# C4F7N_MainBoard.net
KiCad netlist of a schematic drawn in EasyEDA
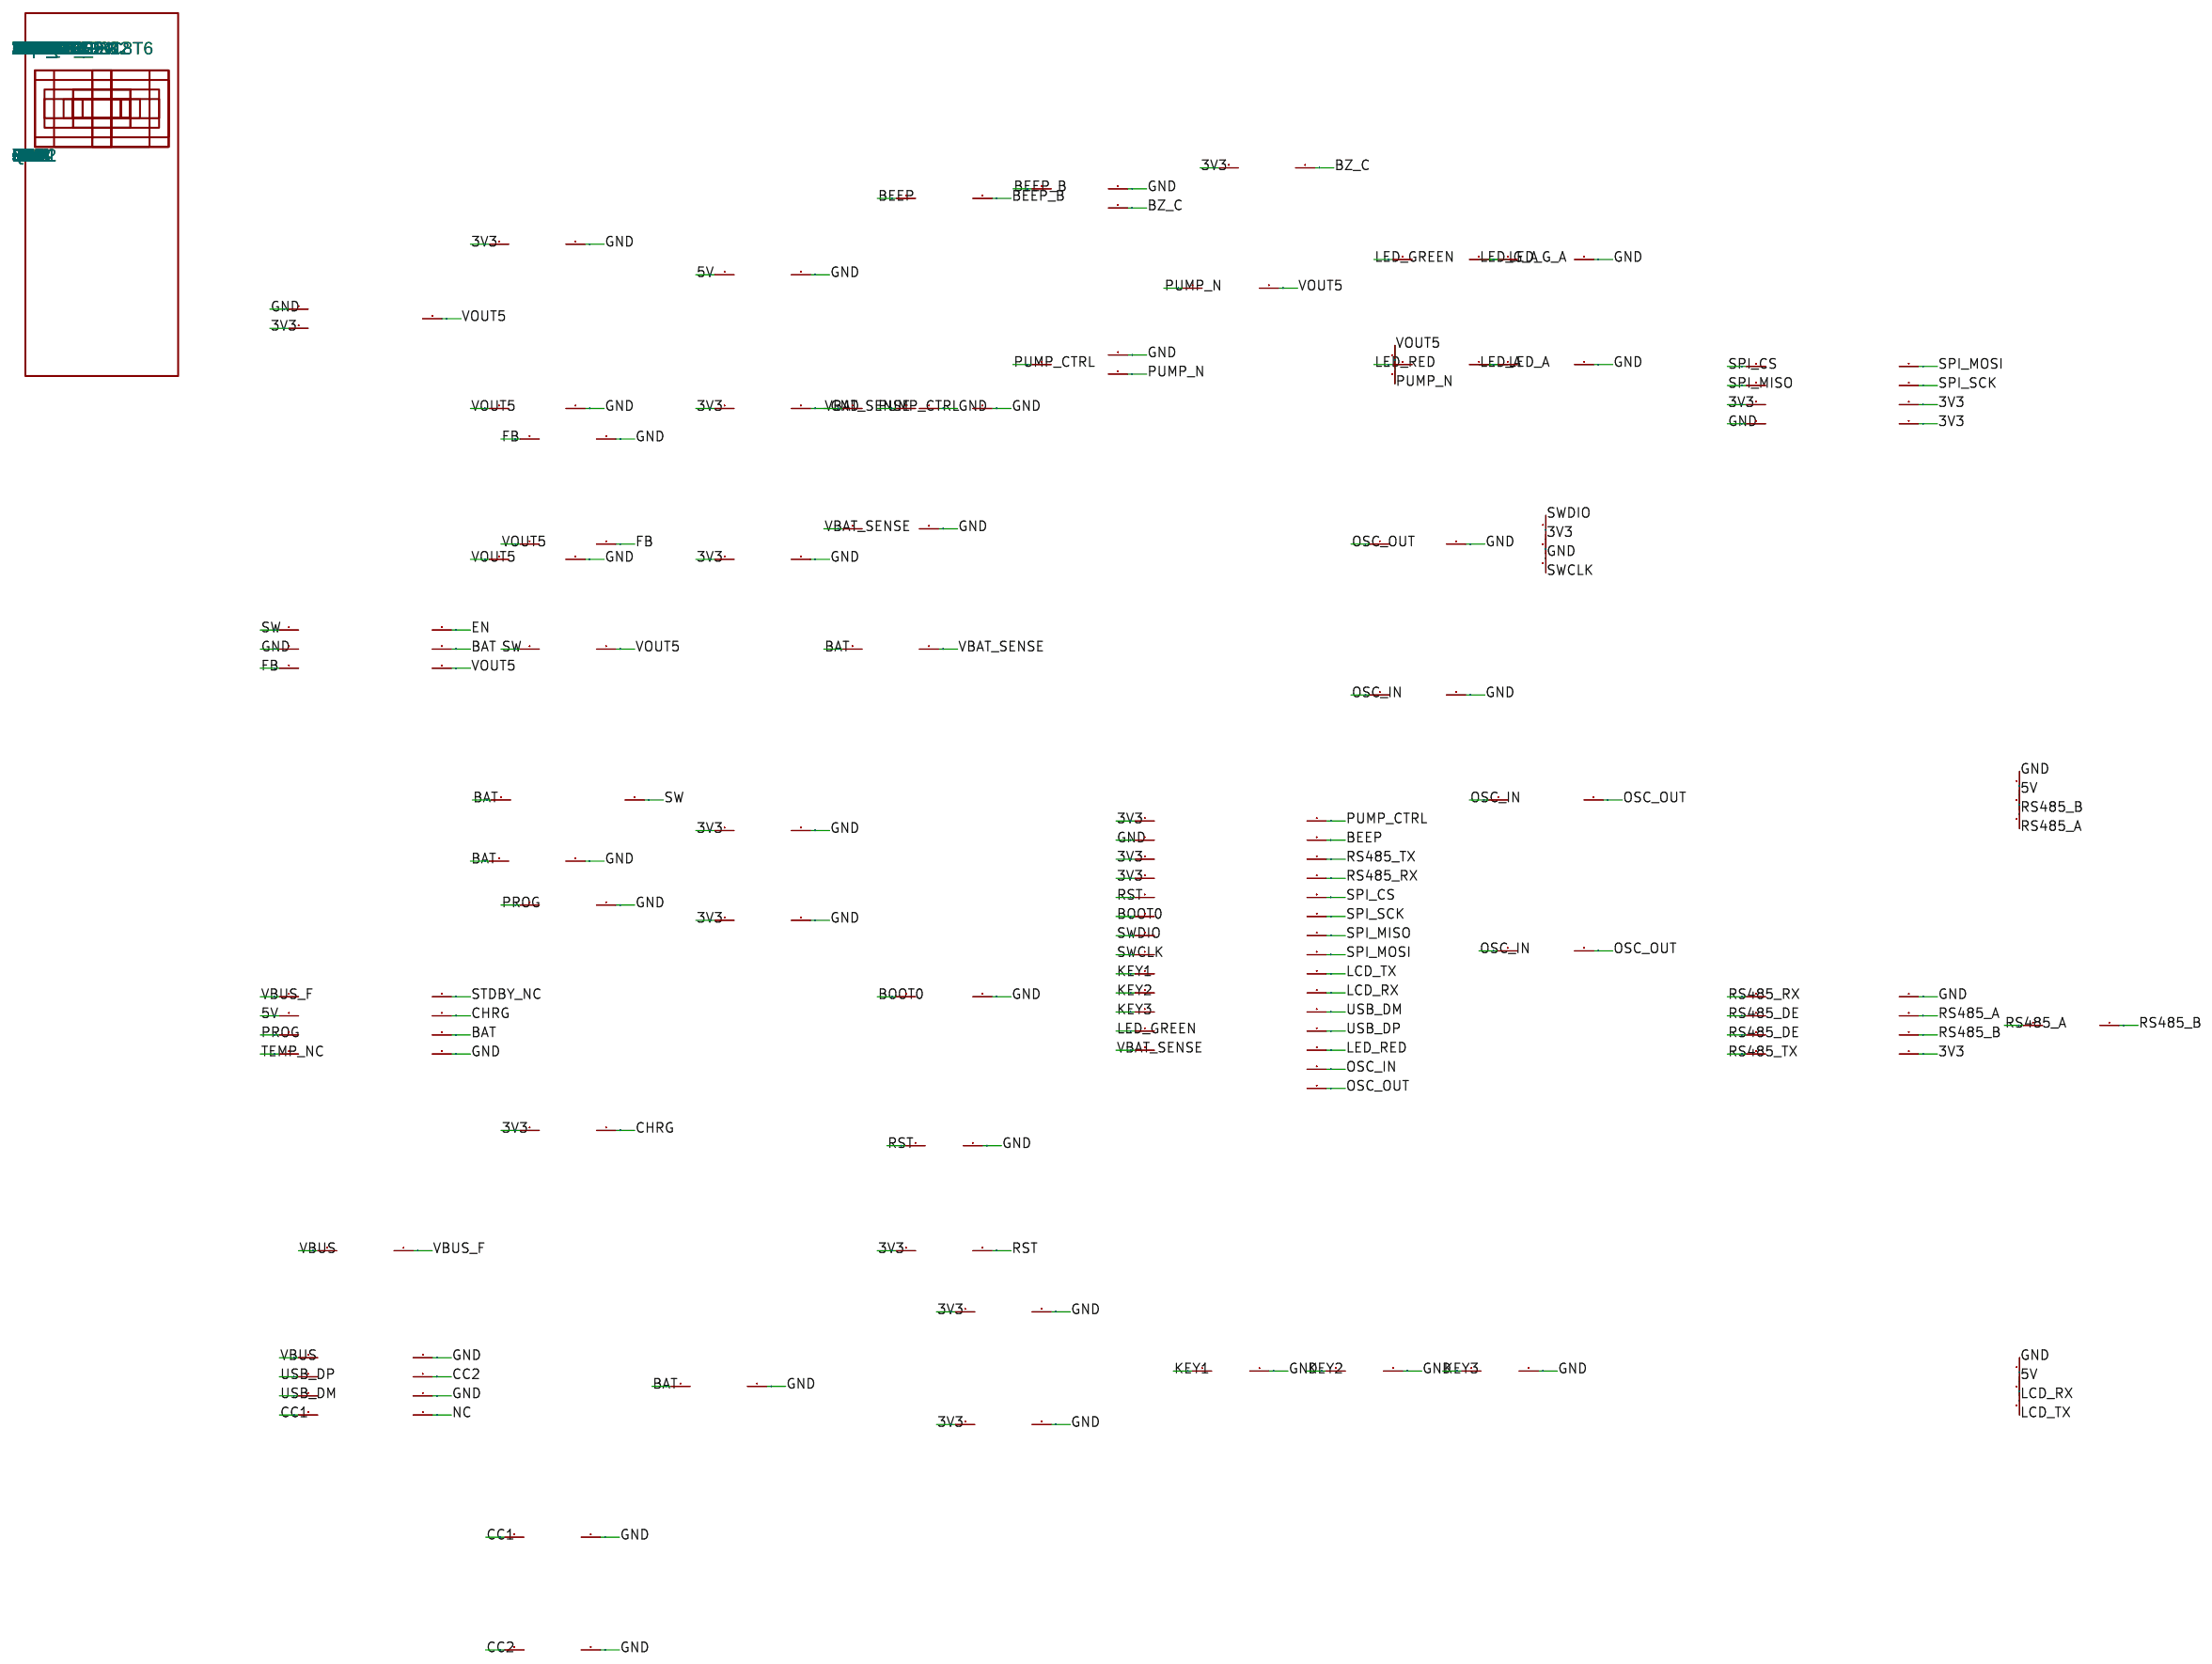
[diagram p0: schematic sheet]

(export (version "E")
  (design (tool "Eeschema 10.0.6"))
  (components
    (comp (ref "BT1") (value "18650x2") (libsource (lib "") (part "Unknown_323_669")))
    (comp (ref "BZ1") (value "BUZZER_5V") (libsource (lib "") (part "Unknown_610_31")))
    (comp (ref "C1") (value "10uF") (libsource (lib "") (part "Unknown_228_394")))
    (comp (ref "C2") (value "22uF") (libsource (lib "") (part "Unknown_228_236")))
    (comp (ref "C3") (value "10uF") (libsource (lib "") (part "Unknown_228_157")))
    (comp (ref "C4") (value "10uF") (libsource (lib "") (part "Unknown_228_71")))
    (comp (ref "C5") (value "100nF") (libsource (lib "") (part "Unknown_346_378")))
    (comp (ref "C6") (value "100nF") (libsource (lib "") (part "Unknown_346_425")))
    (comp (ref "C7") (value "20pF") (libsource (lib "") (part "Unknown_689_307")))
    (comp (ref "C8") (value "20pF") (libsource (lib "") (part "Unknown_689_228")))
    (comp (ref "C9") (value "100nF") (libsource (lib "") (part "Unknown_346_236")))
    (comp (ref "C10") (value "100nF") (libsource (lib "") (part "Unknown_346_157")))
    (comp (ref "C11") (value "100nF") (libsource (lib "") (part "Unknown_472_689")))
    (comp (ref "C12") (value "100nF") (libsource (lib "") (part "Unknown_472_630")))
    (comp (ref "C13") (value "100nF") (libsource (lib "") (part "Unknown_346_87")))
    (comp (ref "C14") (value "100nF") (libsource (lib "") (part "Unknown_413_157")))
    (comp (ref "D1") (value "LED_RED") (libsource (lib "") (part "Unknown_244_535")))
    (comp (ref "D2") (value "SS34") (libsource (lib "") (part "Unknown_244_283")))
    (comp (ref "D3") (value "1N5819") (libsource (lib "") (part "Unknown_591_94")))
    (comp (ref "F1") (value "500mA") (libsource (lib "") (part "Unknown_138_598")))
    (comp (ref "J1") (value "USB-C") (libsource (lib "") (part "Unknown_138_669")))
    (comp (ref "J2") (value "LCD_4.3") (libsource (lib "") (part "Unknown_1004_669")))
    (comp (ref "J3") (value "PROBE_GX12") (libsource (lib "") (part "Unknown_1004_362")))
    (comp (ref "J4") (value "PUMP") (libsource (lib "") (part "Unknown_677_134")))
    (comp (ref "J6") (value "SWD") (libsource (lib "") (part "Unknown_756_228")))
    (comp (ref "L1") (value "10uH") (libsource (lib "") (part "Unknown_244_362")))
    (comp (ref "LED1") (value "LED_RED") (libsource (lib "") (part "Unknown_756_134")))
    (comp (ref "LED2") (value "LED_GREEN") (libsource (lib "") (part "Unknown_756_79")))
    (comp (ref "Q1") (value "SI2302") (libsource (lib "") (part "Unknown_512_134")))
    (comp (ref "Q2") (value "MMBT2222") (libsource (lib "") (part "Unknown_512_47")))
    (comp (ref "R1") (value "1.2k") (libsource (lib "") (part "Unknown_244_417")))
    (comp (ref "R2") (value "100k") (libsource (lib "") (part "Unknown_244_228")))
    (comp (ref "R3") (value "20k") (libsource (lib "") (part "Unknown_244_173")))
    (comp (ref "R4") (value "1M") (libsource (lib "") (part "Unknown_756_441")))
    (comp (ref "R5") (value "10k") (libsource (lib "") (part "Unknown_441_598")))
    (comp (ref "R6") (value "10k") (libsource (lib "") (part "Unknown_441_465")))
    (comp (ref "R9") (value "120R") (libsource (lib "") (part "Unknown_1031_480")))
    (comp (ref "R12") (value "5.1k") (libsource (lib "") (part "Unknown_236_748")))
    (comp (ref "R13") (value "5.1k") (libsource (lib "") (part "Unknown_236_807")))
    (comp (ref "R15") (value "100k") (libsource (lib "") (part "Unknown_441_157")))
    (comp (ref "R16") (value "1k") (libsource (lib "") (part "Unknown_441_47")))
    (comp (ref "R17") (value "330R") (libsource (lib "") (part "Unknown_701_134")))
    (comp (ref "R18") (value "330R") (libsource (lib "") (part "Unknown_701_79")))
    (comp (ref "R22") (value "100k") (libsource (lib "") (part "Unknown_413_283")))
    (comp (ref "R23") (value "100k") (libsource (lib "") (part "Unknown_413_220")))
    (comp (ref "SW1") (value "RESET") (libsource (lib "") (part "Unknown_441_543")))
    (comp (ref "SW2") (value "KEY1") (libsource (lib "") (part "Unknown_591_661")))
    (comp (ref "SW3") (value "KEY2") (libsource (lib "") (part "Unknown_661_661")))
    (comp (ref "SW4") (value "KEY3") (libsource (lib "") (part "Unknown_732_661")))
    (comp (ref "U1") (value "TP4056") (libsource (lib "") (part "Unknown_138_480")))
    (comp (ref "U2") (value "MT3608") (libsource (lib "") (part "Unknown_138_283")))
    (comp (ref "U3") (value "AMS1117-3.3") (libsource (lib "") (part "Unknown_138_110")))
    (comp (ref "U4") (value "STM32F103C8T6") (libsource (lib "") (part "Unknown_591_413")))
    (comp (ref "U5") (value "MAX3485") (libsource (lib "") (part "Unknown_906_480")))
    (comp (ref "U6") (value "W25Q16") (libsource (lib "") (part "Unknown_906_150")))
    (comp (ref "Y1") (value "8MHz") (libsource (lib "") (part "Unknown_756_362")))
  )
  (nets
    (net (code "1") (name "/3V3") (class "Default")
      (node (ref "J2") (pin "2") (pinfunction "2_2") (pintype "unspecified"))
      (node (ref "J3") (pin "2") (pinfunction "2_2") (pintype "unspecified"))
      (node (ref "J6") (pin "2") (pinfunction "2_2") (pintype "unspecified"))
    )
    (net (code "24") (name "/PUMP_N") (class "Default")
      (node (ref "J4") (pin "2") (pinfunction "2_2") (pintype "unspecified"))
    )
    (net (code "40") (name "unconnected-(BT1-Pad2)") (class "Default")
      (node (ref "BT1") (pin "2") (pinfunction "2_2") (pintype "unspecified"))
    )
    (net (code "41") (name "unconnected-(BT1-Pad2)_1") (class "Default")
      (node (ref "BT1") (pin "2") (pinfunction "2_2") (pintype "unspecified"))
    )
    (net (code "42") (name "unconnected-(BZ1-Pad2)") (class "Default")
      (node (ref "BZ1") (pin "2") (pinfunction "2_2") (pintype "unspecified"))
    )
    (net (code "43") (name "unconnected-(BZ1-Pad2)_1") (class "Default")
      (node (ref "BZ1") (pin "2") (pinfunction "2_2") (pintype "unspecified"))
    )
    (net (code "44") (name "unconnected-(C1-Pad2)") (class "Default")
      (node (ref "C1") (pin "2") (pinfunction "2_2") (pintype "unspecified"))
    )
    (net (code "45") (name "unconnected-(C1-Pad2)_1") (class "Default")
      (node (ref "C1") (pin "2") (pinfunction "2_2") (pintype "unspecified"))
    )
    (net (code "46") (name "unconnected-(C2-Pad2)") (class "Default")
      (node (ref "C2") (pin "2") (pinfunction "2_2") (pintype "unspecified"))
    )
    (net (code "47") (name "unconnected-(C2-Pad2)_1") (class "Default")
      (node (ref "C2") (pin "2") (pinfunction "2_2") (pintype "unspecified"))
    )
    (net (code "48") (name "unconnected-(C3-Pad2)") (class "Default")
      (node (ref "C3") (pin "2") (pinfunction "2_2") (pintype "unspecified"))
    )
    (net (code "49") (name "unconnected-(C3-Pad2)_1") (class "Default")
      (node (ref "C3") (pin "2") (pinfunction "2_2") (pintype "unspecified"))
    )
    (net (code "50") (name "unconnected-(C4-Pad2)") (class "Default")
      (node (ref "C4") (pin "2") (pinfunction "2_2") (pintype "unspecified"))
    )
    (net (code "51") (name "unconnected-(C4-Pad2)_1") (class "Default")
      (node (ref "C4") (pin "2") (pinfunction "2_2") (pintype "unspecified"))
    )
    (net (code "52") (name "unconnected-(C5-Pad2)") (class "Default")
      (node (ref "C5") (pin "2") (pinfunction "2_2") (pintype "unspecified"))
    )
    (net (code "53") (name "unconnected-(C5-Pad2)_1") (class "Default")
      (node (ref "C5") (pin "2") (pinfunction "2_2") (pintype "unspecified"))
    )
    (net (code "54") (name "unconnected-(C6-Pad2)") (class "Default")
      (node (ref "C6") (pin "2") (pinfunction "2_2") (pintype "unspecified"))
    )
    (net (code "55") (name "unconnected-(C6-Pad2)_1") (class "Default")
      (node (ref "C6") (pin "2") (pinfunction "2_2") (pintype "unspecified"))
    )
    (net (code "56") (name "unconnected-(C7-Pad2)") (class "Default")
      (node (ref "C7") (pin "2") (pinfunction "2_2") (pintype "unspecified"))
    )
    (net (code "57") (name "unconnected-(C7-Pad2)_1") (class "Default")
      (node (ref "C7") (pin "2") (pinfunction "2_2") (pintype "unspecified"))
    )
    (net (code "58") (name "unconnected-(C8-Pad2)") (class "Default")
      (node (ref "C8") (pin "2") (pinfunction "2_2") (pintype "unspecified"))
    )
    (net (code "59") (name "unconnected-(C8-Pad2)_1") (class "Default")
      (node (ref "C8") (pin "2") (pinfunction "2_2") (pintype "unspecified"))
    )
    (net (code "60") (name "unconnected-(C9-Pad2)") (class "Default")
      (node (ref "C9") (pin "2") (pinfunction "2_2") (pintype "unspecified"))
    )
    (net (code "61") (name "unconnected-(C9-Pad2)_1") (class "Default")
      (node (ref "C9") (pin "2") (pinfunction "2_2") (pintype "unspecified"))
    )
    (net (code "62") (name "unconnected-(C10-Pad2)") (class "Default")
      (node (ref "C10") (pin "2") (pinfunction "2_2") (pintype "unspecified"))
    )
    (net (code "63") (name "unconnected-(C10-Pad2)_1") (class "Default")
      (node (ref "C10") (pin "2") (pinfunction "2_2") (pintype "unspecified"))
    )
    (net (code "64") (name "unconnected-(C11-Pad2)") (class "Default")
      (node (ref "C11") (pin "2") (pinfunction "2_2") (pintype "unspecified"))
    )
    (net (code "65") (name "unconnected-(C11-Pad2)_1") (class "Default")
      (node (ref "C11") (pin "2") (pinfunction "2_2") (pintype "unspecified"))
    )
    (net (code "66") (name "unconnected-(C12-Pad2)") (class "Default")
      (node (ref "C12") (pin "2") (pinfunction "2_2") (pintype "unspecified"))
    )
    (net (code "67") (name "unconnected-(C12-Pad2)_1") (class "Default")
      (node (ref "C12") (pin "2") (pinfunction "2_2") (pintype "unspecified"))
    )
    (net (code "68") (name "unconnected-(C13-Pad2)") (class "Default")
      (node (ref "C13") (pin "2") (pinfunction "2_2") (pintype "unspecified"))
    )
    (net (code "69") (name "unconnected-(C13-Pad2)_1") (class "Default")
      (node (ref "C13") (pin "2") (pinfunction "2_2") (pintype "unspecified"))
    )
    (net (code "70") (name "unconnected-(C14-Pad2)") (class "Default")
      (node (ref "C14") (pin "2") (pinfunction "2_2") (pintype "unspecified"))
    )
    (net (code "71") (name "unconnected-(C14-Pad2)_1") (class "Default")
      (node (ref "C14") (pin "2") (pinfunction "2_2") (pintype "unspecified"))
    )
    (net (code "72") (name "unconnected-(D1-Pad2)") (class "Default")
      (node (ref "D1") (pin "2") (pinfunction "2_2") (pintype "unspecified"))
    )
    (net (code "73") (name "unconnected-(D1-Pad2)_1") (class "Default")
      (node (ref "D1") (pin "2") (pinfunction "2_2") (pintype "unspecified"))
    )
    (net (code "74") (name "unconnected-(D2-Pad2)") (class "Default")
      (node (ref "D2") (pin "2") (pinfunction "2_2") (pintype "unspecified"))
    )
    (net (code "75") (name "unconnected-(D2-Pad2)_1") (class "Default")
      (node (ref "D2") (pin "2") (pinfunction "2_2") (pintype "unspecified"))
    )
    (net (code "76") (name "unconnected-(D3-Pad2)") (class "Default")
      (node (ref "D3") (pin "2") (pinfunction "2_2") (pintype "unspecified"))
    )
    (net (code "77") (name "unconnected-(D3-Pad2)_1") (class "Default")
      (node (ref "D3") (pin "2") (pinfunction "2_2") (pintype "unspecified"))
    )
    (net (code "78") (name "unconnected-(F1-Pad2)") (class "Default")
      (node (ref "F1") (pin "2") (pinfunction "2_2") (pintype "unspecified"))
    )
    (net (code "79") (name "unconnected-(F1-Pad2)_1") (class "Default")
      (node (ref "F1") (pin "2") (pinfunction "2_2") (pintype "unspecified"))
    )
    (net (code "80") (name "unconnected-(J1-Pad2)") (class "Default")
      (node (ref "J1") (pin "2") (pinfunction "2_2") (pintype "unspecified"))
    )
    (net (code "81") (name "unconnected-(J1-Pad2)_1") (class "Default")
      (node (ref "J1") (pin "2") (pinfunction "2_2") (pintype "unspecified"))
    )
    (net (code "82") (name "unconnected-(J1-Pad2)_2") (class "Default")
      (node (ref "J1") (pin "2") (pinfunction "2_2") (pintype "unspecified"))
    )
    (net (code "83") (name "unconnected-(J1-Pad2)_3") (class "Default")
      (node (ref "J1") (pin "2") (pinfunction "2_2") (pintype "unspecified"))
    )
    (net (code "84") (name "unconnected-(J1-Pad2)_4") (class "Default")
      (node (ref "J1") (pin "2") (pinfunction "2_2") (pintype "unspecified"))
    )
    (net (code "85") (name "unconnected-(J1-Pad2)_5") (class "Default")
      (node (ref "J1") (pin "2") (pinfunction "2_2") (pintype "unspecified"))
    )
    (net (code "86") (name "unconnected-(J1-Pad2)_6") (class "Default")
      (node (ref "J1") (pin "2") (pinfunction "2_2") (pintype "unspecified"))
    )
    (net (code "87") (name "unconnected-(J1-Pad2)_7") (class "Default")
      (node (ref "J1") (pin "2") (pinfunction "2_2") (pintype "unspecified"))
    )
    (net (code "88") (name "unconnected-(L1-Pad2)") (class "Default")
      (node (ref "L1") (pin "2") (pinfunction "2_2") (pintype "unspecified"))
    )
    (net (code "89") (name "unconnected-(L1-Pad2)_1") (class "Default")
      (node (ref "L1") (pin "2") (pinfunction "2_2") (pintype "unspecified"))
    )
    (net (code "90") (name "unconnected-(LED1-Pad2)") (class "Default")
      (node (ref "LED1") (pin "2") (pinfunction "2_2") (pintype "unspecified"))
    )
    (net (code "91") (name "unconnected-(LED1-Pad2)_1") (class "Default")
      (node (ref "LED1") (pin "2") (pinfunction "2_2") (pintype "unspecified"))
    )
    (net (code "92") (name "unconnected-(LED2-Pad2)") (class "Default")
      (node (ref "LED2") (pin "2") (pinfunction "2_2") (pintype "unspecified"))
    )
    (net (code "93") (name "unconnected-(LED2-Pad2)_1") (class "Default")
      (node (ref "LED2") (pin "2") (pinfunction "2_2") (pintype "unspecified"))
    )
    (net (code "94") (name "unconnected-(Q1-Pad2)") (class "Default")
      (node (ref "Q1") (pin "2") (pinfunction "2_2") (pintype "unspecified"))
    )
    (net (code "95") (name "unconnected-(Q1-Pad2)_1") (class "Default")
      (node (ref "Q1") (pin "2") (pinfunction "2_2") (pintype "unspecified"))
    )
    (net (code "96") (name "unconnected-(Q1-Pad2)_2") (class "Default")
      (node (ref "Q1") (pin "2") (pinfunction "2_2") (pintype "unspecified"))
    )
    (net (code "97") (name "unconnected-(Q2-Pad2)") (class "Default")
      (node (ref "Q2") (pin "2") (pinfunction "2_2") (pintype "unspecified"))
    )
    (net (code "98") (name "unconnected-(Q2-Pad2)_1") (class "Default")
      (node (ref "Q2") (pin "2") (pinfunction "2_2") (pintype "unspecified"))
    )
    (net (code "99") (name "unconnected-(Q2-Pad2)_2") (class "Default")
      (node (ref "Q2") (pin "2") (pinfunction "2_2") (pintype "unspecified"))
    )
    (net (code "100") (name "unconnected-(R1-Pad2)") (class "Default")
      (node (ref "R1") (pin "2") (pinfunction "2_2") (pintype "unspecified"))
    )
    (net (code "101") (name "unconnected-(R1-Pad2)_1") (class "Default")
      (node (ref "R1") (pin "2") (pinfunction "2_2") (pintype "unspecified"))
    )
    (net (code "102") (name "unconnected-(R2-Pad2)") (class "Default")
      (node (ref "R2") (pin "2") (pinfunction "2_2") (pintype "unspecified"))
    )
    (net (code "103") (name "unconnected-(R2-Pad2)_1") (class "Default")
      (node (ref "R2") (pin "2") (pinfunction "2_2") (pintype "unspecified"))
    )
    (net (code "104") (name "unconnected-(R3-Pad2)") (class "Default")
      (node (ref "R3") (pin "2") (pinfunction "2_2") (pintype "unspecified"))
    )
    (net (code "105") (name "unconnected-(R3-Pad2)_1") (class "Default")
      (node (ref "R3") (pin "2") (pinfunction "2_2") (pintype "unspecified"))
    )
    (net (code "106") (name "unconnected-(R4-Pad2)") (class "Default")
      (node (ref "R4") (pin "2") (pinfunction "2_2") (pintype "unspecified"))
    )
    (net (code "107") (name "unconnected-(R4-Pad2)_1") (class "Default")
      (node (ref "R4") (pin "2") (pinfunction "2_2") (pintype "unspecified"))
    )
    (net (code "108") (name "unconnected-(R5-Pad2)") (class "Default")
      (node (ref "R5") (pin "2") (pinfunction "2_2") (pintype "unspecified"))
    )
    (net (code "109") (name "unconnected-(R5-Pad2)_1") (class "Default")
      (node (ref "R5") (pin "2") (pinfunction "2_2") (pintype "unspecified"))
    )
    (net (code "110") (name "unconnected-(R6-Pad2)") (class "Default")
      (node (ref "R6") (pin "2") (pinfunction "2_2") (pintype "unspecified"))
    )
    (net (code "111") (name "unconnected-(R6-Pad2)_1") (class "Default")
      (node (ref "R6") (pin "2") (pinfunction "2_2") (pintype "unspecified"))
    )
    (net (code "112") (name "unconnected-(R9-Pad2)") (class "Default")
      (node (ref "R9") (pin "2") (pinfunction "2_2") (pintype "unspecified"))
    )
    (net (code "113") (name "unconnected-(R9-Pad2)_1") (class "Default")
      (node (ref "R9") (pin "2") (pinfunction "2_2") (pintype "unspecified"))
    )
    (net (code "114") (name "unconnected-(R12-Pad2)") (class "Default")
      (node (ref "R12") (pin "2") (pinfunction "2_2") (pintype "unspecified"))
    )
    (net (code "115") (name "unconnected-(R12-Pad2)_1") (class "Default")
      (node (ref "R12") (pin "2") (pinfunction "2_2") (pintype "unspecified"))
    )
    (net (code "116") (name "unconnected-(R13-Pad2)") (class "Default")
      (node (ref "R13") (pin "2") (pinfunction "2_2") (pintype "unspecified"))
    )
    (net (code "117") (name "unconnected-(R13-Pad2)_1") (class "Default")
      (node (ref "R13") (pin "2") (pinfunction "2_2") (pintype "unspecified"))
    )
    (net (code "118") (name "unconnected-(R15-Pad2)") (class "Default")
      (node (ref "R15") (pin "2") (pinfunction "2_2") (pintype "unspecified"))
    )
    (net (code "119") (name "unconnected-(R15-Pad2)_1") (class "Default")
      (node (ref "R15") (pin "2") (pinfunction "2_2") (pintype "unspecified"))
    )
    (net (code "120") (name "unconnected-(R16-Pad2)") (class "Default")
      (node (ref "R16") (pin "2") (pinfunction "2_2") (pintype "unspecified"))
    )
    (net (code "121") (name "unconnected-(R16-Pad2)_1") (class "Default")
      (node (ref "R16") (pin "2") (pinfunction "2_2") (pintype "unspecified"))
    )
    (net (code "122") (name "unconnected-(R17-Pad2)") (class "Default")
      (node (ref "R17") (pin "2") (pinfunction "2_2") (pintype "unspecified"))
    )
    (net (code "123") (name "unconnected-(R17-Pad2)_1") (class "Default")
      (node (ref "R17") (pin "2") (pinfunction "2_2") (pintype "unspecified"))
    )
    (net (code "124") (name "unconnected-(R18-Pad2)") (class "Default")
      (node (ref "R18") (pin "2") (pinfunction "2_2") (pintype "unspecified"))
    )
    (net (code "125") (name "unconnected-(R18-Pad2)_1") (class "Default")
      (node (ref "R18") (pin "2") (pinfunction "2_2") (pintype "unspecified"))
    )
    (net (code "126") (name "unconnected-(R22-Pad2)") (class "Default")
      (node (ref "R22") (pin "2") (pinfunction "2_2") (pintype "unspecified"))
    )
    (net (code "127") (name "unconnected-(R22-Pad2)_1") (class "Default")
      (node (ref "R22") (pin "2") (pinfunction "2_2") (pintype "unspecified"))
    )
    (net (code "128") (name "unconnected-(R23-Pad2)") (class "Default")
      (node (ref "R23") (pin "2") (pinfunction "2_2") (pintype "unspecified"))
    )
    (net (code "129") (name "unconnected-(R23-Pad2)_1") (class "Default")
      (node (ref "R23") (pin "2") (pinfunction "2_2") (pintype "unspecified"))
    )
    (net (code "130") (name "unconnected-(SW1-Pad2)") (class "Default")
      (node (ref "SW1") (pin "2") (pinfunction "2_2") (pintype "unspecified"))
    )
    (net (code "131") (name "unconnected-(SW1-Pad2)_1") (class "Default")
      (node (ref "SW1") (pin "2") (pinfunction "2_2") (pintype "unspecified"))
    )
    (net (code "132") (name "unconnected-(SW2-Pad2)") (class "Default")
      (node (ref "SW2") (pin "2") (pinfunction "2_2") (pintype "unspecified"))
    )
    (net (code "133") (name "unconnected-(SW2-Pad2)_1") (class "Default")
      (node (ref "SW2") (pin "2") (pinfunction "2_2") (pintype "unspecified"))
    )
    (net (code "134") (name "unconnected-(SW3-Pad2)") (class "Default")
      (node (ref "SW3") (pin "2") (pinfunction "2_2") (pintype "unspecified"))
    )
    (net (code "135") (name "unconnected-(SW3-Pad2)_1") (class "Default")
      (node (ref "SW3") (pin "2") (pinfunction "2_2") (pintype "unspecified"))
    )
    (net (code "136") (name "unconnected-(SW4-Pad2)") (class "Default")
      (node (ref "SW4") (pin "2") (pinfunction "2_2") (pintype "unspecified"))
    )
    (net (code "137") (name "unconnected-(SW4-Pad2)_1") (class "Default")
      (node (ref "SW4") (pin "2") (pinfunction "2_2") (pintype "unspecified"))
    )
    (net (code "138") (name "unconnected-(U1-Pad2)") (class "Default")
      (node (ref "U1") (pin "2") (pinfunction "2_2") (pintype "unspecified"))
    )
    (net (code "139") (name "unconnected-(U1-Pad2)_1") (class "Default")
      (node (ref "U1") (pin "2") (pinfunction "2_2") (pintype "unspecified"))
    )
    (net (code "140") (name "unconnected-(U1-Pad2)_2") (class "Default")
      (node (ref "U1") (pin "2") (pinfunction "2_2") (pintype "unspecified"))
    )
    (net (code "141") (name "unconnected-(U1-Pad2)_3") (class "Default")
      (node (ref "U1") (pin "2") (pinfunction "2_2") (pintype "unspecified"))
    )
    (net (code "142") (name "unconnected-(U1-Pad2)_4") (class "Default")
      (node (ref "U1") (pin "2") (pinfunction "2_2") (pintype "unspecified"))
    )
    (net (code "143") (name "unconnected-(U1-Pad2)_5") (class "Default")
      (node (ref "U1") (pin "2") (pinfunction "2_2") (pintype "unspecified"))
    )
    (net (code "144") (name "unconnected-(U1-Pad2)_6") (class "Default")
      (node (ref "U1") (pin "2") (pinfunction "2_2") (pintype "unspecified"))
    )
    (net (code "145") (name "unconnected-(U1-Pad2)_7") (class "Default")
      (node (ref "U1") (pin "2") (pinfunction "2_2") (pintype "unspecified"))
    )
    (net (code "146") (name "unconnected-(U2-Pad2)") (class "Default")
      (node (ref "U2") (pin "2") (pinfunction "2_2") (pintype "unspecified"))
    )
    (net (code "147") (name "unconnected-(U2-Pad2)_1") (class "Default")
      (node (ref "U2") (pin "2") (pinfunction "2_2") (pintype "unspecified"))
    )
    (net (code "148") (name "unconnected-(U2-Pad2)_2") (class "Default")
      (node (ref "U2") (pin "2") (pinfunction "2_2") (pintype "unspecified"))
    )
    (net (code "149") (name "unconnected-(U2-Pad2)_3") (class "Default")
      (node (ref "U2") (pin "2") (pinfunction "2_2") (pintype "unspecified"))
    )
    (net (code "150") (name "unconnected-(U2-Pad2)_4") (class "Default")
      (node (ref "U2") (pin "2") (pinfunction "2_2") (pintype "unspecified"))
    )
    (net (code "151") (name "unconnected-(U2-Pad2)_5") (class "Default")
      (node (ref "U2") (pin "2") (pinfunction "2_2") (pintype "unspecified"))
    )
    (net (code "152") (name "unconnected-(U3-Pad2)") (class "Default")
      (node (ref "U3") (pin "2") (pinfunction "2_2") (pintype "unspecified"))
    )
    (net (code "153") (name "unconnected-(U3-Pad2)_1") (class "Default")
      (node (ref "U3") (pin "2") (pinfunction "2_2") (pintype "unspecified"))
    )
    (net (code "154") (name "unconnected-(U3-Pad2)_2") (class "Default")
      (node (ref "U3") (pin "2") (pinfunction "2_2") (pintype "unspecified"))
    )
    (net (code "155") (name "unconnected-(U4-Pad2)") (class "Default")
      (node (ref "U4") (pin "2") (pinfunction "2_2") (pintype "unspecified"))
    )
    (net (code "156") (name "unconnected-(U4-Pad2)_1") (class "Default")
      (node (ref "U4") (pin "2") (pinfunction "2_2") (pintype "unspecified"))
    )
    (net (code "157") (name "unconnected-(U4-Pad2)_2") (class "Default")
      (node (ref "U4") (pin "2") (pinfunction "2_2") (pintype "unspecified"))
    )
    (net (code "158") (name "unconnected-(U4-Pad2)_3") (class "Default")
      (node (ref "U4") (pin "2") (pinfunction "2_2") (pintype "unspecified"))
    )
    (net (code "159") (name "unconnected-(U4-Pad2)_4") (class "Default")
      (node (ref "U4") (pin "2") (pinfunction "2_2") (pintype "unspecified"))
    )
    (net (code "160") (name "unconnected-(U4-Pad2)_5") (class "Default")
      (node (ref "U4") (pin "2") (pinfunction "2_2") (pintype "unspecified"))
    )
    (net (code "161") (name "unconnected-(U4-Pad2)_6") (class "Default")
      (node (ref "U4") (pin "2") (pinfunction "2_2") (pintype "unspecified"))
    )
    (net (code "162") (name "unconnected-(U4-Pad2)_7") (class "Default")
      (node (ref "U4") (pin "2") (pinfunction "2_2") (pintype "unspecified"))
    )
    (net (code "163") (name "unconnected-(U4-Pad2)_8") (class "Default")
      (node (ref "U4") (pin "2") (pinfunction "2_2") (pintype "unspecified"))
    )
    (net (code "164") (name "unconnected-(U4-Pad2)_9") (class "Default")
      (node (ref "U4") (pin "2") (pinfunction "2_2") (pintype "unspecified"))
    )
    (net (code "165") (name "unconnected-(U4-Pad2)_10") (class "Default")
      (node (ref "U4") (pin "2") (pinfunction "2_2") (pintype "unspecified"))
    )
    (net (code "166") (name "unconnected-(U4-Pad2)_11") (class "Default")
      (node (ref "U4") (pin "2") (pinfunction "2_2") (pintype "unspecified"))
    )
    (net (code "167") (name "unconnected-(U4-Pad2)_12") (class "Default")
      (node (ref "U4") (pin "2") (pinfunction "2_2") (pintype "unspecified"))
    )
    (net (code "168") (name "unconnected-(U4-Pad2)_13") (class "Default")
      (node (ref "U4") (pin "2") (pinfunction "2_2") (pintype "unspecified"))
    )
    (net (code "169") (name "unconnected-(U4-Pad2)_14") (class "Default")
      (node (ref "U4") (pin "2") (pinfunction "2_2") (pintype "unspecified"))
    )
    (net (code "170") (name "unconnected-(U4-Pad2)_15") (class "Default")
      (node (ref "U4") (pin "2") (pinfunction "2_2") (pintype "unspecified"))
    )
    (net (code "171") (name "unconnected-(U4-Pad2)_16") (class "Default")
      (node (ref "U4") (pin "2") (pinfunction "2_2") (pintype "unspecified"))
    )
    (net (code "172") (name "unconnected-(U4-Pad2)_17") (class "Default")
      (node (ref "U4") (pin "2") (pinfunction "2_2") (pintype "unspecified"))
    )
    (net (code "173") (name "unconnected-(U4-Pad2)_18") (class "Default")
      (node (ref "U4") (pin "2") (pinfunction "2_2") (pintype "unspecified"))
    )
    (net (code "174") (name "unconnected-(U4-Pad2)_19") (class "Default")
      (node (ref "U4") (pin "2") (pinfunction "2_2") (pintype "unspecified"))
    )
    (net (code "175") (name "unconnected-(U4-Pad2)_20") (class "Default")
      (node (ref "U4") (pin "2") (pinfunction "2_2") (pintype "unspecified"))
    )
    (net (code "176") (name "unconnected-(U4-Pad2)_21") (class "Default")
      (node (ref "U4") (pin "2") (pinfunction "2_2") (pintype "unspecified"))
    )
    (net (code "177") (name "unconnected-(U4-Pad2)_22") (class "Default")
      (node (ref "U4") (pin "2") (pinfunction "2_2") (pintype "unspecified"))
    )
    (net (code "178") (name "unconnected-(U4-Pad2)_23") (class "Default")
      (node (ref "U4") (pin "2") (pinfunction "2_2") (pintype "unspecified"))
    )
    (net (code "179") (name "unconnected-(U4-Pad2)_24") (class "Default")
      (node (ref "U4") (pin "2") (pinfunction "2_2") (pintype "unspecified"))
    )
    (net (code "180") (name "unconnected-(U4-Pad2)_25") (class "Default")
      (node (ref "U4") (pin "2") (pinfunction "2_2") (pintype "unspecified"))
    )
    (net (code "181") (name "unconnected-(U4-Pad2)_26") (class "Default")
      (node (ref "U4") (pin "2") (pinfunction "2_2") (pintype "unspecified"))
    )
    (net (code "182") (name "unconnected-(U4-Pad2)_27") (class "Default")
      (node (ref "U4") (pin "2") (pinfunction "2_2") (pintype "unspecified"))
    )
    (net (code "183") (name "unconnected-(U5-Pad2)") (class "Default")
      (node (ref "U5") (pin "2") (pinfunction "2_2") (pintype "unspecified"))
    )
    (net (code "184") (name "unconnected-(U5-Pad2)_1") (class "Default")
      (node (ref "U5") (pin "2") (pinfunction "2_2") (pintype "unspecified"))
    )
    (net (code "185") (name "unconnected-(U5-Pad2)_2") (class "Default")
      (node (ref "U5") (pin "2") (pinfunction "2_2") (pintype "unspecified"))
    )
    (net (code "186") (name "unconnected-(U5-Pad2)_3") (class "Default")
      (node (ref "U5") (pin "2") (pinfunction "2_2") (pintype "unspecified"))
    )
    (net (code "187") (name "unconnected-(U5-Pad2)_4") (class "Default")
      (node (ref "U5") (pin "2") (pinfunction "2_2") (pintype "unspecified"))
    )
    (net (code "188") (name "unconnected-(U5-Pad2)_5") (class "Default")
      (node (ref "U5") (pin "2") (pinfunction "2_2") (pintype "unspecified"))
    )
    (net (code "189") (name "unconnected-(U5-Pad2)_6") (class "Default")
      (node (ref "U5") (pin "2") (pinfunction "2_2") (pintype "unspecified"))
    )
    (net (code "190") (name "unconnected-(U5-Pad2)_7") (class "Default")
      (node (ref "U5") (pin "2") (pinfunction "2_2") (pintype "unspecified"))
    )
    (net (code "191") (name "unconnected-(U6-Pad2)") (class "Default")
      (node (ref "U6") (pin "2") (pinfunction "2_2") (pintype "unspecified"))
    )
    (net (code "192") (name "unconnected-(U6-Pad2)_1") (class "Default")
      (node (ref "U6") (pin "2") (pinfunction "2_2") (pintype "unspecified"))
    )
    (net (code "193") (name "unconnected-(U6-Pad2)_2") (class "Default")
      (node (ref "U6") (pin "2") (pinfunction "2_2") (pintype "unspecified"))
    )
    (net (code "194") (name "unconnected-(U6-Pad2)_3") (class "Default")
      (node (ref "U6") (pin "2") (pinfunction "2_2") (pintype "unspecified"))
    )
    (net (code "195") (name "unconnected-(U6-Pad2)_4") (class "Default")
      (node (ref "U6") (pin "2") (pinfunction "2_2") (pintype "unspecified"))
    )
    (net (code "196") (name "unconnected-(U6-Pad2)_5") (class "Default")
      (node (ref "U6") (pin "2") (pinfunction "2_2") (pintype "unspecified"))
    )
    (net (code "197") (name "unconnected-(U6-Pad2)_6") (class "Default")
      (node (ref "U6") (pin "2") (pinfunction "2_2") (pintype "unspecified"))
    )
    (net (code "198") (name "unconnected-(U6-Pad2)_7") (class "Default")
      (node (ref "U6") (pin "2") (pinfunction "2_2") (pintype "unspecified"))
    )
    (net (code "199") (name "unconnected-(Y1-Pad2)") (class "Default")
      (node (ref "Y1") (pin "2") (pinfunction "2_2") (pintype "unspecified"))
    )
    (net (code "200") (name "unconnected-(Y1-Pad2)_1") (class "Default")
      (node (ref "Y1") (pin "2") (pinfunction "2_2") (pintype "unspecified"))
    )
  )
)
